# main.net
KiCad netlist of a schematic drawn in EAGLE
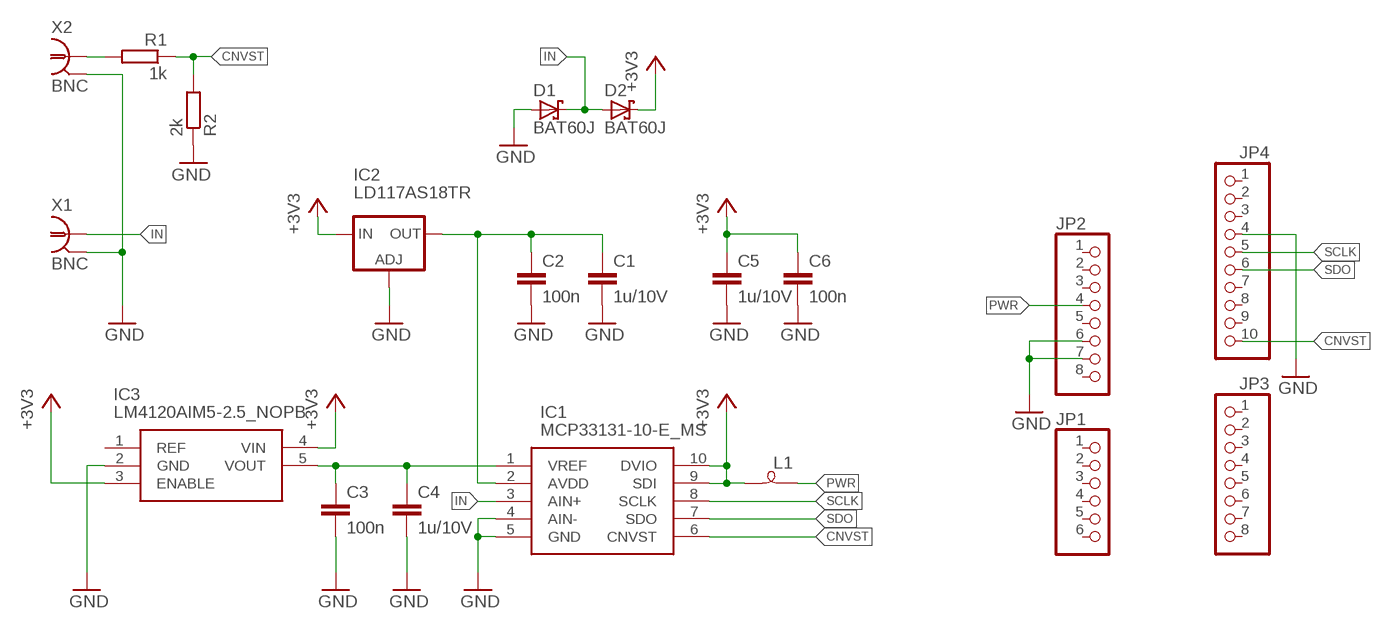
[diagram p0: schematic, sheet 1]

(export (version "E")
  (design (tool "Eeschema 10.0.6"))
  (components
    (comp (ref "C1")
      (value "1u/10V")
      (footprint "eagle-import:C1206")
      (libsource (lib "eagle-import") (part "C-EUC1206"))
    )
    (comp (ref "C2")
      (value "100n")
      (footprint "eagle-import:C0805")
      (libsource (lib "eagle-import") (part "C-EUC0805"))
    )
    (comp (ref "C3")
      (value "100n")
      (footprint "eagle-import:C0805")
      (libsource (lib "eagle-import") (part "C-EUC0805"))
    )
    (comp (ref "C4")
      (value "1u/10V")
      (footprint "eagle-import:C1206")
      (libsource (lib "eagle-import") (part "C-EUC1206"))
    )
    (comp (ref "C5")
      (value "1u/10V")
      (footprint "eagle-import:C1206")
      (libsource (lib "eagle-import") (part "C-EUC1206"))
    )
    (comp (ref "C6")
      (value "100n")
      (footprint "eagle-import:C0805")
      (libsource (lib "eagle-import") (part "C-EUC0805"))
    )
    (comp (ref "D1")
      (value "BAT60J")
      (footprint "eagle-import:SOD323_ST")
      (libsource (lib "eagle-import") (part "BAT60J"))
    )
    (comp (ref "D2")
      (value "BAT60J")
      (footprint "eagle-import:SOD323_ST")
      (libsource (lib "eagle-import") (part "BAT60J"))
    )
    (comp (ref "IC1")
      (value "MCP33131-10-E_MS")
      (footprint "eagle-import:SOP50P490X110-10N")
      (fields
        (field (name "MANUFACTURER_PART_NUMBER") "MCP33131-10-E/MS")
        (field (name "MOUSER_PART_NUMBER") "579-MCP33131-10-E/MS")
      )
      (libsource (lib "eagle-import") (part "MCP33131-10-E_MS"))
    )
    (comp (ref "IC2")
      (value "LD117AS18TR")
      (footprint "eagle-import:SOT223")
      (libsource (lib "eagle-import") (part "LD117A?S18TR"))
    )
    (comp (ref "IC3")
      (value "LM4120AIM5-2.5_NOPB")
      (footprint "eagle-import:SOT95P280X145-5N")
      (fields
        (field (name "MANUFACTURER_PART_NUMBER") "LM4120AIM5-2.5/NOPB")
        (field (name "MOUSER_PART_NUMBER") "926-LM4120AIM525NOPB")
      )
      (libsource (lib "eagle-import") (part "LM4120AIM5-2.5_NOPB"))
    )
    (comp (ref "JP1")
      (value "PINHD-1X6")
      (footprint "eagle-import:1X06")
      (libsource (lib "eagle-import") (part "PINHD-1X6"))
    )
    (comp (ref "JP2")
      (value "PINHD-1X8")
      (footprint "eagle-import:1X08")
      (libsource (lib "eagle-import") (part "PINHD-1X8"))
    )
    (comp (ref "JP3")
      (value "PINHD-1X8")
      (footprint "eagle-import:1X08")
      (libsource (lib "eagle-import") (part "PINHD-1X8"))
    )
    (comp (ref "JP4")
      (value "PINHD-1X10")
      (footprint "eagle-import:1X10")
      (libsource (lib "eagle-import") (part "PINHD-1X10"))
    )
    (comp (ref "L1")
      (value "SM-B5")
      (footprint "eagle-import:SM-B5")
      (libsource (lib "eagle-import") (part "SM-B5"))
    )
    (comp (ref "R1")
      (value "1k")
      (footprint "eagle-import:R0805")
      (libsource (lib "eagle-import") (part "R-EU_R0805"))
    )
    (comp (ref "R2")
      (value "2k")
      (footprint "eagle-import:R0805")
      (libsource (lib "eagle-import") (part "R-EU_R0805"))
    )
    (comp (ref "X1")
      (value "BNC")
      (footprint "eagle-import:AMP_227161")
      (libsource (lib "eagle-import") (part "?2271611--2"))
    )
    (comp (ref "X2")
      (value "BNC")
      (footprint "eagle-import:AMP_227161")
      (libsource (lib "eagle-import") (part "?2271611--2"))
    )
  )
  (nets
    (net (code "1") (name "+3V3") (class "Default")
      (node (ref "C5") (pin "1") (pinfunction "1_1") (pintype "passive"))
      (node (ref "C6") (pin "1") (pinfunction "1_1") (pintype "passive"))
      (node (ref "D2") (pin "C") (pinfunction "C_C") (pintype "passive"))
      (node (ref "IC1") (pin "10") (pinfunction "DVIO_10") (pintype "bidirectional"))
      (node (ref "IC1") (pin "9") (pinfunction "SDI_9") (pintype "bidirectional"))
      (node (ref "IC2") (pin "3") (pinfunction "IN_3") (pintype "input"))
      (node (ref "IC3") (pin "3") (pinfunction "ENABLE_3") (pintype "bidirectional"))
      (node (ref "IC3") (pin "4") (pinfunction "VIN_4") (pintype "bidirectional"))
      (node (ref "L1") (pin "2") (pinfunction "2_2") (pintype "passive"))
    )
    (net (code "2") (name "CNVST") (class "Default")
      (node (ref "IC1") (pin "6") (pinfunction "CNVST_6") (pintype "bidirectional"))
      (node (ref "JP4") (pin "10") (pinfunction "10_10") (pintype "passive"))
      (node (ref "R1") (pin "1") (pinfunction "1_1") (pintype "passive"))
      (node (ref "R2") (pin "2") (pinfunction "2_2") (pintype "passive"))
    )
    (net (code "3") (name "GND") (class "Default")
      (node (ref "C1") (pin "2") (pinfunction "2_2") (pintype "passive"))
      (node (ref "C2") (pin "2") (pinfunction "2_2") (pintype "passive"))
      (node (ref "C3") (pin "2") (pinfunction "2_2") (pintype "passive"))
      (node (ref "C4") (pin "2") (pinfunction "2_2") (pintype "passive"))
      (node (ref "C5") (pin "2") (pinfunction "2_2") (pintype "passive"))
      (node (ref "C6") (pin "2") (pinfunction "2_2") (pintype "passive"))
      (node (ref "D1") (pin "A") (pinfunction "A_A") (pintype "passive"))
      (node (ref "IC1") (pin "4") (pinfunction "AIN-_4") (pintype "bidirectional"))
      (node (ref "IC1") (pin "5") (pinfunction "GND_5") (pintype "power_in"))
      (node (ref "IC2") (pin "1") (pinfunction "ADJ_1") (pintype "input"))
      (node (ref "IC3") (pin "2") (pinfunction "GND_2") (pintype "bidirectional"))
      (node (ref "JP2") (pin "6") (pinfunction "6_6") (pintype "passive"))
      (node (ref "JP2") (pin "7") (pinfunction "7_7") (pintype "passive"))
      (node (ref "JP4") (pin "4") (pinfunction "4_4") (pintype "passive"))
      (node (ref "R2") (pin "1") (pinfunction "1_1") (pintype "passive"))
      (node (ref "X1") (pin "2") (pinfunction "2_2") (pintype "passive"))
      (node (ref "X2") (pin "2") (pinfunction "2_2") (pintype "passive"))
    )
    (net (code "4") (name "IN") (class "Default")
      (node (ref "D1") (pin "C") (pinfunction "C_C") (pintype "passive"))
      (node (ref "D2") (pin "A") (pinfunction "A_A") (pintype "passive"))
      (node (ref "IC1") (pin "3") (pinfunction "AIN+_3") (pintype "bidirectional"))
      (node (ref "X1") (pin "1") (pinfunction "1_1") (pintype "passive"))
    )
    (net (code "5") (name "Net-(IC1-AVDD)") (class "Default")
      (node (ref "C1") (pin "1") (pinfunction "1_1") (pintype "passive"))
      (node (ref "C2") (pin "1") (pinfunction "1_1") (pintype "passive"))
      (node (ref "IC1") (pin "2") (pinfunction "AVDD_2") (pintype "bidirectional"))
      (node (ref "IC2") (pin "4") (pinfunction "OUT_4") (pintype "passive"))
    )
    (net (code "6") (name "Net-(IC1-VREF)") (class "Default")
      (node (ref "C3") (pin "1") (pinfunction "1_1") (pintype "passive"))
      (node (ref "C4") (pin "1") (pinfunction "1_1") (pintype "passive"))
      (node (ref "IC1") (pin "1") (pinfunction "VREF_1") (pintype "bidirectional"))
      (node (ref "IC3") (pin "5") (pinfunction "VOUT_5") (pintype "bidirectional"))
    )
    (net (code "7") (name "Net-(R1-Pad2)") (class "Default")
      (node (ref "R1") (pin "2") (pinfunction "2_2") (pintype "passive"))
      (node (ref "X2") (pin "1") (pinfunction "1_1") (pintype "passive"))
    )
    (net (code "8") (name "PWR") (class "Default")
      (node (ref "JP2") (pin "4") (pinfunction "4_4") (pintype "passive"))
      (node (ref "L1") (pin "1") (pinfunction "1_1") (pintype "passive"))
    )
    (net (code "9") (name "SCLK") (class "Default")
      (node (ref "IC1") (pin "8") (pinfunction "SCLK_8") (pintype "bidirectional"))
      (node (ref "JP4") (pin "5") (pinfunction "5_5") (pintype "passive"))
    )
    (net (code "10") (name "SDO") (class "Default")
      (node (ref "IC1") (pin "7") (pinfunction "SDO_7") (pintype "bidirectional"))
      (node (ref "JP4") (pin "6") (pinfunction "6_6") (pintype "passive"))
    )
    (net (code "11") (name "unconnected-(IC3-REF-Pad1)") (class "Default")
      (node (ref "IC3") (pin "1") (pinfunction "REF_1") (pintype "bidirectional"))
    )
    (net (code "12") (name "unconnected-(JP1-Pad1)") (class "Default")
      (node (ref "JP1") (pin "1") (pinfunction "1_1") (pintype "passive"))
    )
    (net (code "13") (name "unconnected-(JP1-Pad2)") (class "Default")
      (node (ref "JP1") (pin "2") (pinfunction "2_2") (pintype "passive"))
    )
    (net (code "14") (name "unconnected-(JP1-Pad3)") (class "Default")
      (node (ref "JP1") (pin "3") (pinfunction "3_3") (pintype "passive"))
    )
    (net (code "15") (name "unconnected-(JP1-Pad4)") (class "Default")
      (node (ref "JP1") (pin "4") (pinfunction "4_4") (pintype "passive"))
    )
    (net (code "16") (name "unconnected-(JP1-Pad5)") (class "Default")
      (node (ref "JP1") (pin "5") (pinfunction "5_5") (pintype "passive"))
    )
    (net (code "17") (name "unconnected-(JP1-Pad6)") (class "Default")
      (node (ref "JP1") (pin "6") (pinfunction "6_6") (pintype "passive"))
    )
    (net (code "18") (name "unconnected-(JP2-Pad1)") (class "Default")
      (node (ref "JP2") (pin "1") (pinfunction "1_1") (pintype "passive"))
    )
    (net (code "19") (name "unconnected-(JP2-Pad2)") (class "Default")
      (node (ref "JP2") (pin "2") (pinfunction "2_2") (pintype "passive"))
    )
    (net (code "20") (name "unconnected-(JP2-Pad3)") (class "Default")
      (node (ref "JP2") (pin "3") (pinfunction "3_3") (pintype "passive"))
    )
    (net (code "21") (name "unconnected-(JP2-Pad5)") (class "Default")
      (node (ref "JP2") (pin "5") (pinfunction "5_5") (pintype "passive"))
    )
    (net (code "22") (name "unconnected-(JP2-Pad8)") (class "Default")
      (node (ref "JP2") (pin "8") (pinfunction "8_8") (pintype "passive"))
    )
    (net (code "23") (name "unconnected-(JP3-Pad1)") (class "Default")
      (node (ref "JP3") (pin "1") (pinfunction "1_1") (pintype "passive"))
    )
    (net (code "24") (name "unconnected-(JP3-Pad2)") (class "Default")
      (node (ref "JP3") (pin "2") (pinfunction "2_2") (pintype "passive"))
    )
    (net (code "25") (name "unconnected-(JP3-Pad3)") (class "Default")
      (node (ref "JP3") (pin "3") (pinfunction "3_3") (pintype "passive"))
    )
    (net (code "26") (name "unconnected-(JP3-Pad4)") (class "Default")
      (node (ref "JP3") (pin "4") (pinfunction "4_4") (pintype "passive"))
    )
    (net (code "27") (name "unconnected-(JP3-Pad5)") (class "Default")
      (node (ref "JP3") (pin "5") (pinfunction "5_5") (pintype "passive"))
    )
    (net (code "28") (name "unconnected-(JP3-Pad6)") (class "Default")
      (node (ref "JP3") (pin "6") (pinfunction "6_6") (pintype "passive"))
    )
    (net (code "29") (name "unconnected-(JP3-Pad7)") (class "Default")
      (node (ref "JP3") (pin "7") (pinfunction "7_7") (pintype "passive"))
    )
    (net (code "30") (name "unconnected-(JP3-Pad8)") (class "Default")
      (node (ref "JP3") (pin "8") (pinfunction "8_8") (pintype "passive"))
    )
    (net (code "31") (name "unconnected-(JP4-Pad1)") (class "Default")
      (node (ref "JP4") (pin "1") (pinfunction "1_1") (pintype "passive"))
    )
    (net (code "32") (name "unconnected-(JP4-Pad2)") (class "Default")
      (node (ref "JP4") (pin "2") (pinfunction "2_2") (pintype "passive"))
    )
    (net (code "33") (name "unconnected-(JP4-Pad3)") (class "Default")
      (node (ref "JP4") (pin "3") (pinfunction "3_3") (pintype "passive"))
    )
    (net (code "34") (name "unconnected-(JP4-Pad7)") (class "Default")
      (node (ref "JP4") (pin "7") (pinfunction "7_7") (pintype "passive"))
    )
    (net (code "35") (name "unconnected-(JP4-Pad8)") (class "Default")
      (node (ref "JP4") (pin "8") (pinfunction "8_8") (pintype "passive"))
    )
    (net (code "36") (name "unconnected-(JP4-Pad9)") (class "Default")
      (node (ref "JP4") (pin "9") (pinfunction "9_9") (pintype "passive"))
    )
  )
)
